# octosonar.net
KiCad netlist of a schematic drawn in EAGLE
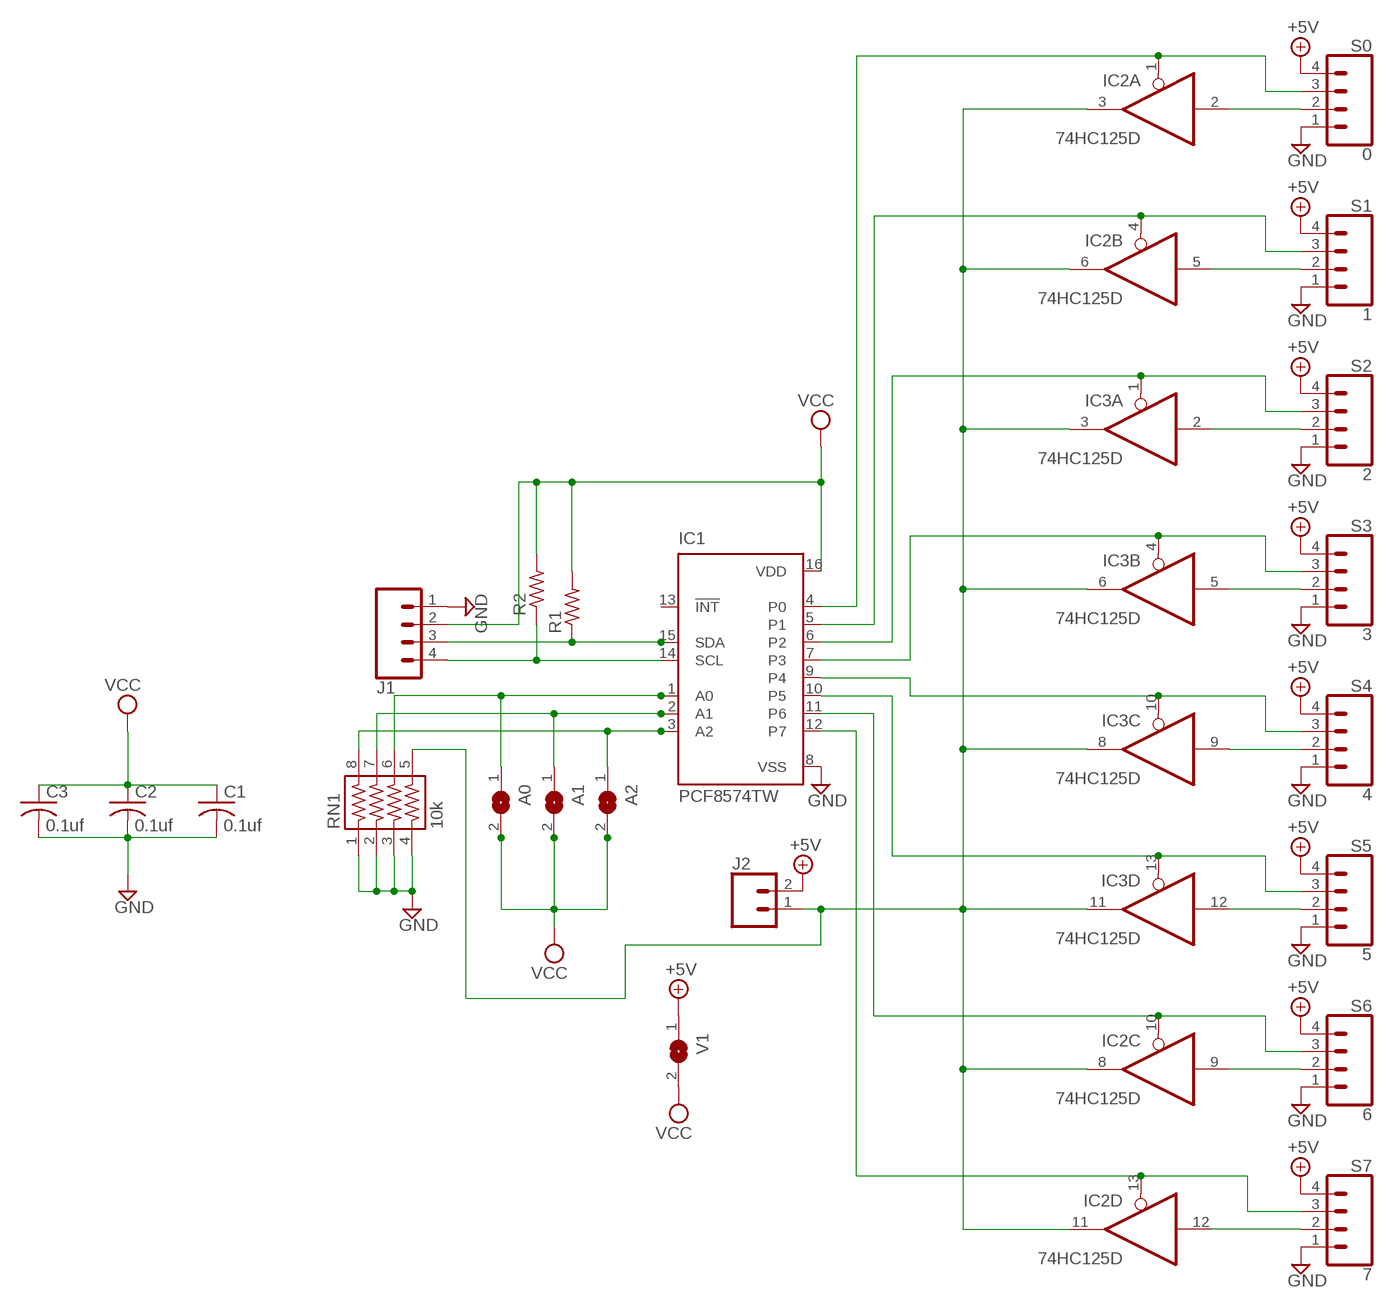
[diagram p0: schematic, sheet 1]

(export (version "E")
  (design (tool "Eeschema 10.0.6"))
  (components
    (comp (ref "A0") (value "SJ") (footprint "eagle-import:SJ") (libsource (lib "eagle-import") (part "SJ")))
    (comp (ref "A1") (value "SJ") (footprint "eagle-import:SJ") (libsource (lib "eagle-import") (part "SJ")))
    (comp (ref "A2") (value "SJ") (footprint "eagle-import:SJ") (libsource (lib "eagle-import") (part "SJ")))
    (comp (ref "C1")
      (value "0.1uf")
      (footprint "eagle-import:C0805")
      (libsource (lib "eagle-import") (part "C-USC0805"))
    )
    (comp (ref "C2")
      (value "0.1uf")
      (footprint "eagle-import:C0805")
      (libsource (lib "eagle-import") (part "C-USC0805"))
    )
    (comp (ref "C3")
      (value "0.1uf")
      (footprint "eagle-import:C0805")
      (libsource (lib "eagle-import") (part "C-USC0805"))
    )
    (comp (ref "IC1")
      (value "PCF8574TW")
      (footprint "eagle-import:SO16W")
      (fields (field (name "MPN") "PCF8574T/3,512"))
      (libsource (lib "eagle-import") (part "PCF8574TW"))
    )
    (comp (ref "IC2")
      (value "74HC125D")
      (footprint "eagle-import:SO14")
      (libsource (lib "eagle-import") (part "74125DHC"))
    )
    (comp (ref "IC3")
      (value "74HC125D")
      (footprint "eagle-import:SO14")
      (libsource (lib "eagle-import") (part "74xx-eu_85_74125DHC"))
    )
    (comp (ref "J1")
      (value "CONN_04POLAR_LOCK")
      (footprint "eagle-import:MOLEX-1X4_LOCK")
      (libsource (lib "eagle-import") (part "CONN_04POLAR_LOCK"))
    )
    (comp (ref "J2")
      (value "CONN_02POLAR_LOCK")
      (footprint "eagle-import:MOLEX-1X2_LOCK")
      (libsource (lib "eagle-import") (part "CONN_02POLAR_LOCK"))
    )
    (comp (ref "R1")
      (value "R-US_0204/2V")
      (footprint "eagle-import:0204V")
      (libsource (lib "eagle-import") (part "R-US_0204/2V"))
    )
    (comp (ref "R2")
      (value "R-US_0204/2V")
      (footprint "eagle-import:0204V")
      (libsource (lib "eagle-import") (part "R-US_0204/2V"))
    )
    (comp (ref "RN1")
      (value "10k")
      (footprint "eagle-import:743-8")
      (libsource (lib "eagle-import") (part "743-8"))
    )
    (comp (ref "S0")
      (value "0")
      (footprint "eagle-import:MOLEX-1X4_LOCK")
      (libsource (lib "eagle-import") (part "CONN_04POLAR_LOCK"))
    )
    (comp (ref "S1")
      (value "1")
      (footprint "eagle-import:MOLEX-1X4_LOCK")
      (libsource (lib "eagle-import") (part "CONN_04POLAR_LOCK"))
    )
    (comp (ref "S2")
      (value "2")
      (footprint "eagle-import:MOLEX-1X4_LOCK")
      (libsource (lib "eagle-import") (part "CONN_04POLAR_LOCK"))
    )
    (comp (ref "S3")
      (value "3")
      (footprint "eagle-import:MOLEX-1X4_LOCK")
      (libsource (lib "eagle-import") (part "CONN_04POLAR_LOCK"))
    )
    (comp (ref "S4")
      (value "4")
      (footprint "eagle-import:MOLEX-1X4_LOCK")
      (libsource (lib "eagle-import") (part "CONN_04POLAR_LOCK"))
    )
    (comp (ref "S5")
      (value "5")
      (footprint "eagle-import:MOLEX-1X4_LOCK")
      (libsource (lib "eagle-import") (part "CONN_04POLAR_LOCK"))
    )
    (comp (ref "S6")
      (value "6")
      (footprint "eagle-import:MOLEX-1X4_LOCK")
      (libsource (lib "eagle-import") (part "CONN_04POLAR_LOCK"))
    )
    (comp (ref "S7")
      (value "7")
      (footprint "eagle-import:MOLEX-1X4_LOCK")
      (libsource (lib "eagle-import") (part "CONN_04POLAR_LOCK"))
    )
    (comp (ref "V1") (value "SJ") (footprint "eagle-import:SJ") (libsource (lib "eagle-import") (part "SJ")))
  )
  (nets
    (net (code "1") (name "+5V") (class "Default")
      (node (ref "J2") (pin "2") (pinfunction "2_2") (pintype "passive"))
      (node (ref "S0") (pin "4") (pinfunction "4_4") (pintype "passive"))
      (node (ref "S1") (pin "4") (pinfunction "4_4") (pintype "passive"))
      (node (ref "S2") (pin "4") (pinfunction "4_4") (pintype "passive"))
      (node (ref "S3") (pin "4") (pinfunction "4_4") (pintype "passive"))
      (node (ref "S4") (pin "4") (pinfunction "4_4") (pintype "passive"))
      (node (ref "S5") (pin "4") (pinfunction "4_4") (pintype "passive"))
      (node (ref "S6") (pin "4") (pinfunction "4_4") (pintype "passive"))
      (node (ref "S7") (pin "4") (pinfunction "4_4") (pintype "passive"))
      (node (ref "V1") (pin "1") (pinfunction "1_1") (pintype "passive"))
    )
    (net (code "2") (name "GND") (class "Default")
      (node (ref "C1") (pin "2") (pinfunction "2_2") (pintype "passive"))
      (node (ref "C2") (pin "2") (pinfunction "2_2") (pintype "passive"))
      (node (ref "C3") (pin "2") (pinfunction "2_2") (pintype "passive"))
      (node (ref "IC1") (pin "8") (pinfunction "VSS_8") (pintype "power_in"))
      (node (ref "J1") (pin "1") (pinfunction "1_1") (pintype "passive"))
      (node (ref "RN1") (pin "1") (pinfunction "1_1") (pintype "passive"))
      (node (ref "RN1") (pin "2") (pinfunction "2_2") (pintype "passive"))
      (node (ref "RN1") (pin "3") (pinfunction "3_3") (pintype "passive"))
      (node (ref "RN1") (pin "4") (pinfunction "4_4") (pintype "passive"))
      (node (ref "S0") (pin "1") (pinfunction "1_1") (pintype "passive"))
      (node (ref "S1") (pin "1") (pinfunction "1_1") (pintype "passive"))
      (node (ref "S2") (pin "1") (pinfunction "1_1") (pintype "passive"))
      (node (ref "S3") (pin "1") (pinfunction "1_1") (pintype "passive"))
      (node (ref "S4") (pin "1") (pinfunction "1_1") (pintype "passive"))
      (node (ref "S5") (pin "1") (pinfunction "1_1") (pintype "passive"))
      (node (ref "S6") (pin "1") (pinfunction "1_1") (pintype "passive"))
      (node (ref "S7") (pin "1") (pinfunction "1_1") (pintype "passive"))
    )
    (net (code "3") (name "Net-(IC1-A0)") (class "Default")
      (node (ref "A0") (pin "1") (pinfunction "1_1") (pintype "passive"))
      (node (ref "IC1") (pin "1") (pinfunction "A0_1") (pintype "input"))
      (node (ref "RN1") (pin "6") (pinfunction "6_6") (pintype "passive"))
    )
    (net (code "4") (name "Net-(IC1-A1)") (class "Default")
      (node (ref "A1") (pin "1") (pinfunction "1_1") (pintype "passive"))
      (node (ref "IC1") (pin "2") (pinfunction "A1_2") (pintype "input"))
      (node (ref "RN1") (pin "7") (pinfunction "7_7") (pintype "passive"))
    )
    (net (code "5") (name "Net-(IC1-A2)") (class "Default")
      (node (ref "A2") (pin "1") (pinfunction "1_1") (pintype "passive"))
      (node (ref "IC1") (pin "3") (pinfunction "A2_3") (pintype "input"))
      (node (ref "RN1") (pin "8") (pinfunction "8_8") (pintype "passive"))
    )
    (net (code "6") (name "Net-(IC1-P0)") (class "Default")
      (node (ref "IC1") (pin "4") (pinfunction "P0_4") (pintype "bidirectional"))
      (node (ref "IC2") (pin "1") (pinfunction "OE_1") (pintype "input"))
      (node (ref "S0") (pin "3") (pinfunction "3_3") (pintype "passive"))
    )
    (net (code "7") (name "Net-(IC1-P1)") (class "Default")
      (node (ref "IC1") (pin "5") (pinfunction "P1_5") (pintype "bidirectional"))
      (node (ref "IC2") (pin "4") (pinfunction "OE_4") (pintype "input"))
      (node (ref "S1") (pin "3") (pinfunction "3_3") (pintype "passive"))
    )
    (net (code "8") (name "Net-(IC1-P2)") (class "Default")
      (node (ref "IC1") (pin "6") (pinfunction "P2_6") (pintype "bidirectional"))
      (node (ref "IC3") (pin "1") (pinfunction "OE_1") (pintype "input"))
      (node (ref "S2") (pin "3") (pinfunction "3_3") (pintype "passive"))
    )
    (net (code "9") (name "Net-(IC1-P3)") (class "Default")
      (node (ref "IC1") (pin "7") (pinfunction "P3_7") (pintype "bidirectional"))
      (node (ref "IC3") (pin "4") (pinfunction "OE_4") (pintype "input"))
      (node (ref "S3") (pin "3") (pinfunction "3_3") (pintype "passive"))
    )
    (net (code "10") (name "Net-(IC1-P4)") (class "Default")
      (node (ref "IC1") (pin "9") (pinfunction "P4_9") (pintype "bidirectional"))
      (node (ref "IC3") (pin "10") (pinfunction "OE_10") (pintype "input"))
      (node (ref "S4") (pin "3") (pinfunction "3_3") (pintype "passive"))
    )
    (net (code "11") (name "Net-(IC1-P5)") (class "Default")
      (node (ref "IC1") (pin "10") (pinfunction "P5_10") (pintype "bidirectional"))
      (node (ref "IC3") (pin "13") (pinfunction "OE_13") (pintype "input"))
      (node (ref "S5") (pin "3") (pinfunction "3_3") (pintype "passive"))
    )
    (net (code "12") (name "Net-(IC1-P6)") (class "Default")
      (node (ref "IC1") (pin "11") (pinfunction "P6_11") (pintype "bidirectional"))
      (node (ref "IC2") (pin "10") (pinfunction "OE_10") (pintype "input"))
      (node (ref "S6") (pin "3") (pinfunction "3_3") (pintype "passive"))
    )
    (net (code "13") (name "Net-(IC1-P7)") (class "Default")
      (node (ref "IC1") (pin "12") (pinfunction "P7_12") (pintype "bidirectional"))
      (node (ref "IC2") (pin "13") (pinfunction "OE_13") (pintype "input"))
      (node (ref "S7") (pin "3") (pinfunction "3_3") (pintype "passive"))
    )
    (net (code "14") (name "Net-(IC1-SCL)") (class "Default")
      (node (ref "IC1") (pin "14") (pinfunction "SCL_14") (pintype "input"))
      (node (ref "J1") (pin "4") (pinfunction "4_4") (pintype "passive"))
      (node (ref "R2") (pin "1") (pinfunction "1_1") (pintype "passive"))
    )
    (net (code "15") (name "Net-(IC1-SDA)") (class "Default")
      (node (ref "IC1") (pin "15") (pinfunction "SDA_15") (pintype "bidirectional"))
      (node (ref "J1") (pin "3") (pinfunction "3_3") (pintype "passive"))
      (node (ref "R1") (pin "1") (pinfunction "1_1") (pintype "passive"))
    )
    (net (code "16") (name "Net-(IC2A-I)") (class "Default")
      (node (ref "IC2") (pin "2") (pinfunction "I_2") (pintype "input"))
      (node (ref "S0") (pin "2") (pinfunction "2_2") (pintype "passive"))
    )
    (net (code "17") (name "Net-(IC2A-O)") (class "Default")
      (node (ref "IC2") (pin "11") (pinfunction "O_11") (pintype "tri_state"))
      (node (ref "IC2") (pin "3") (pinfunction "O_3") (pintype "tri_state"))
      (node (ref "IC2") (pin "6") (pinfunction "O_6") (pintype "tri_state"))
      (node (ref "IC2") (pin "8") (pinfunction "O_8") (pintype "tri_state"))
      (node (ref "IC3") (pin "11") (pinfunction "O_11") (pintype "tri_state"))
      (node (ref "IC3") (pin "3") (pinfunction "O_3") (pintype "tri_state"))
      (node (ref "IC3") (pin "6") (pinfunction "O_6") (pintype "tri_state"))
      (node (ref "IC3") (pin "8") (pinfunction "O_8") (pintype "tri_state"))
      (node (ref "J2") (pin "1") (pinfunction "1_1") (pintype "passive"))
      (node (ref "RN1") (pin "5") (pinfunction "5_5") (pintype "passive"))
    )
    (net (code "18") (name "Net-(IC2B-I)") (class "Default")
      (node (ref "IC2") (pin "5") (pinfunction "I_5") (pintype "input"))
      (node (ref "S1") (pin "2") (pinfunction "2_2") (pintype "passive"))
    )
    (net (code "19") (name "Net-(IC2C-I)") (class "Default")
      (node (ref "IC2") (pin "9") (pinfunction "I_9") (pintype "input"))
      (node (ref "S6") (pin "2") (pinfunction "2_2") (pintype "passive"))
    )
    (net (code "20") (name "Net-(IC2D-I)") (class "Default")
      (node (ref "IC2") (pin "12") (pinfunction "I_12") (pintype "input"))
      (node (ref "S7") (pin "2") (pinfunction "2_2") (pintype "passive"))
    )
    (net (code "21") (name "Net-(IC3A-I)") (class "Default")
      (node (ref "IC3") (pin "2") (pinfunction "I_2") (pintype "input"))
      (node (ref "S2") (pin "2") (pinfunction "2_2") (pintype "passive"))
    )
    (net (code "22") (name "Net-(IC3B-I)") (class "Default")
      (node (ref "IC3") (pin "5") (pinfunction "I_5") (pintype "input"))
      (node (ref "S3") (pin "2") (pinfunction "2_2") (pintype "passive"))
    )
    (net (code "23") (name "Net-(IC3C-I)") (class "Default")
      (node (ref "IC3") (pin "9") (pinfunction "I_9") (pintype "input"))
      (node (ref "S4") (pin "2") (pinfunction "2_2") (pintype "passive"))
    )
    (net (code "24") (name "Net-(IC3D-I)") (class "Default")
      (node (ref "IC3") (pin "12") (pinfunction "I_12") (pintype "input"))
      (node (ref "S5") (pin "2") (pinfunction "2_2") (pintype "passive"))
    )
    (net (code "25") (name "VCC") (class "Default")
      (node (ref "A0") (pin "2") (pinfunction "2_2") (pintype "passive"))
      (node (ref "A1") (pin "2") (pinfunction "2_2") (pintype "passive"))
      (node (ref "A2") (pin "2") (pinfunction "2_2") (pintype "passive"))
      (node (ref "C1") (pin "1") (pinfunction "1_1") (pintype "passive"))
      (node (ref "C2") (pin "1") (pinfunction "1_1") (pintype "passive"))
      (node (ref "C3") (pin "1") (pinfunction "1_1") (pintype "passive"))
      (node (ref "IC1") (pin "16") (pinfunction "VDD_16") (pintype "power_in"))
      (node (ref "J1") (pin "2") (pinfunction "2_2") (pintype "passive"))
      (node (ref "R1") (pin "2") (pinfunction "2_2") (pintype "passive"))
      (node (ref "R2") (pin "2") (pinfunction "2_2") (pintype "passive"))
      (node (ref "V1") (pin "2") (pinfunction "2_2") (pintype "passive"))
    )
    (net (code "26") (name "unconnected-(IC1-~{INT}-Pad13)") (class "Default")
      (node (ref "IC1") (pin "13") (pinfunction "~{INT}_13") (pintype "output"))
    )
  )
)
